# example2_PassBand.net
KiCad netlist of a schematic drawn in EAGLE
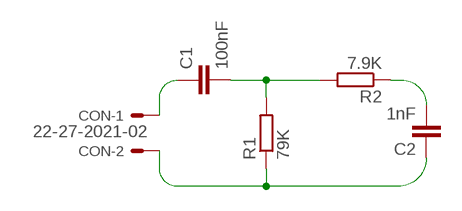
[diagram p0: schematic, sheet 1]

(export (version "E")
  (design (tool "Eeschema 10.0.6"))
  (components
    (comp (ref "C1")
      (value "100nF")
      (footprint "eagle-import:C5B2.5")
      (libsource (lib "eagle-import") (part "C5/2.5"))
    )
    (comp (ref "C2")
      (value "1nF")
      (footprint "eagle-import:C5B2.5")
      (libsource (lib "eagle-import") (part "C5/2.5"))
    )
    (comp (ref "CON")
      (value "22-27-2021-02")
      (footprint "eagle-import:6410-02")
      (fields (field (name "MF") "MOLEX"))
      (libsource (lib "eagle-import") (part "22-?-0227-2021"))
    )
    (comp (ref "R1")
      (value "79K")
      (footprint "eagle-import:0204_7")
      (libsource (lib "eagle-import") (part "R-EU_0204/7"))
    )
    (comp (ref "R2")
      (value "7.9K")
      (footprint "eagle-import:0204_7")
      (libsource (lib "eagle-import") (part "R-EU_0204/7"))
    )
  )
  (nets
    (net (code "1") (name "Net-(C1-Pad2)") (class "Default")
      (node (ref "C1") (pin "2") (pinfunction "2_2") (pintype "passive"))
      (node (ref "R1") (pin "2") (pinfunction "2_2") (pintype "passive"))
      (node (ref "R2") (pin "2") (pinfunction "2_2") (pintype "passive"))
    )
    (net (code "2") (name "Net-(C2-Pad2)") (class "Default")
      (node (ref "C2") (pin "2") (pinfunction "2_2") (pintype "passive"))
      (node (ref "R2") (pin "1") (pinfunction "1_1") (pintype "passive"))
    )
    (net (code "3") (name "Net-(CONA-S)") (class "Default")
      (node (ref "C1") (pin "1") (pinfunction "1_1") (pintype "passive"))
      (node (ref "CON") (pin "1") (pinfunction "S_1") (pintype "passive"))
    )
    (net (code "4") (name "Net-(CONB-S)") (class "Default")
      (node (ref "C2") (pin "1") (pinfunction "1_1") (pintype "passive"))
      (node (ref "CON") (pin "2") (pinfunction "S_2") (pintype "passive"))
      (node (ref "R1") (pin "1") (pinfunction "1_1") (pintype "passive"))
    )
  )
)
